# SCH_Shreder_2023-07-20.net
KiCad netlist of a schematic drawn in EasyEDA
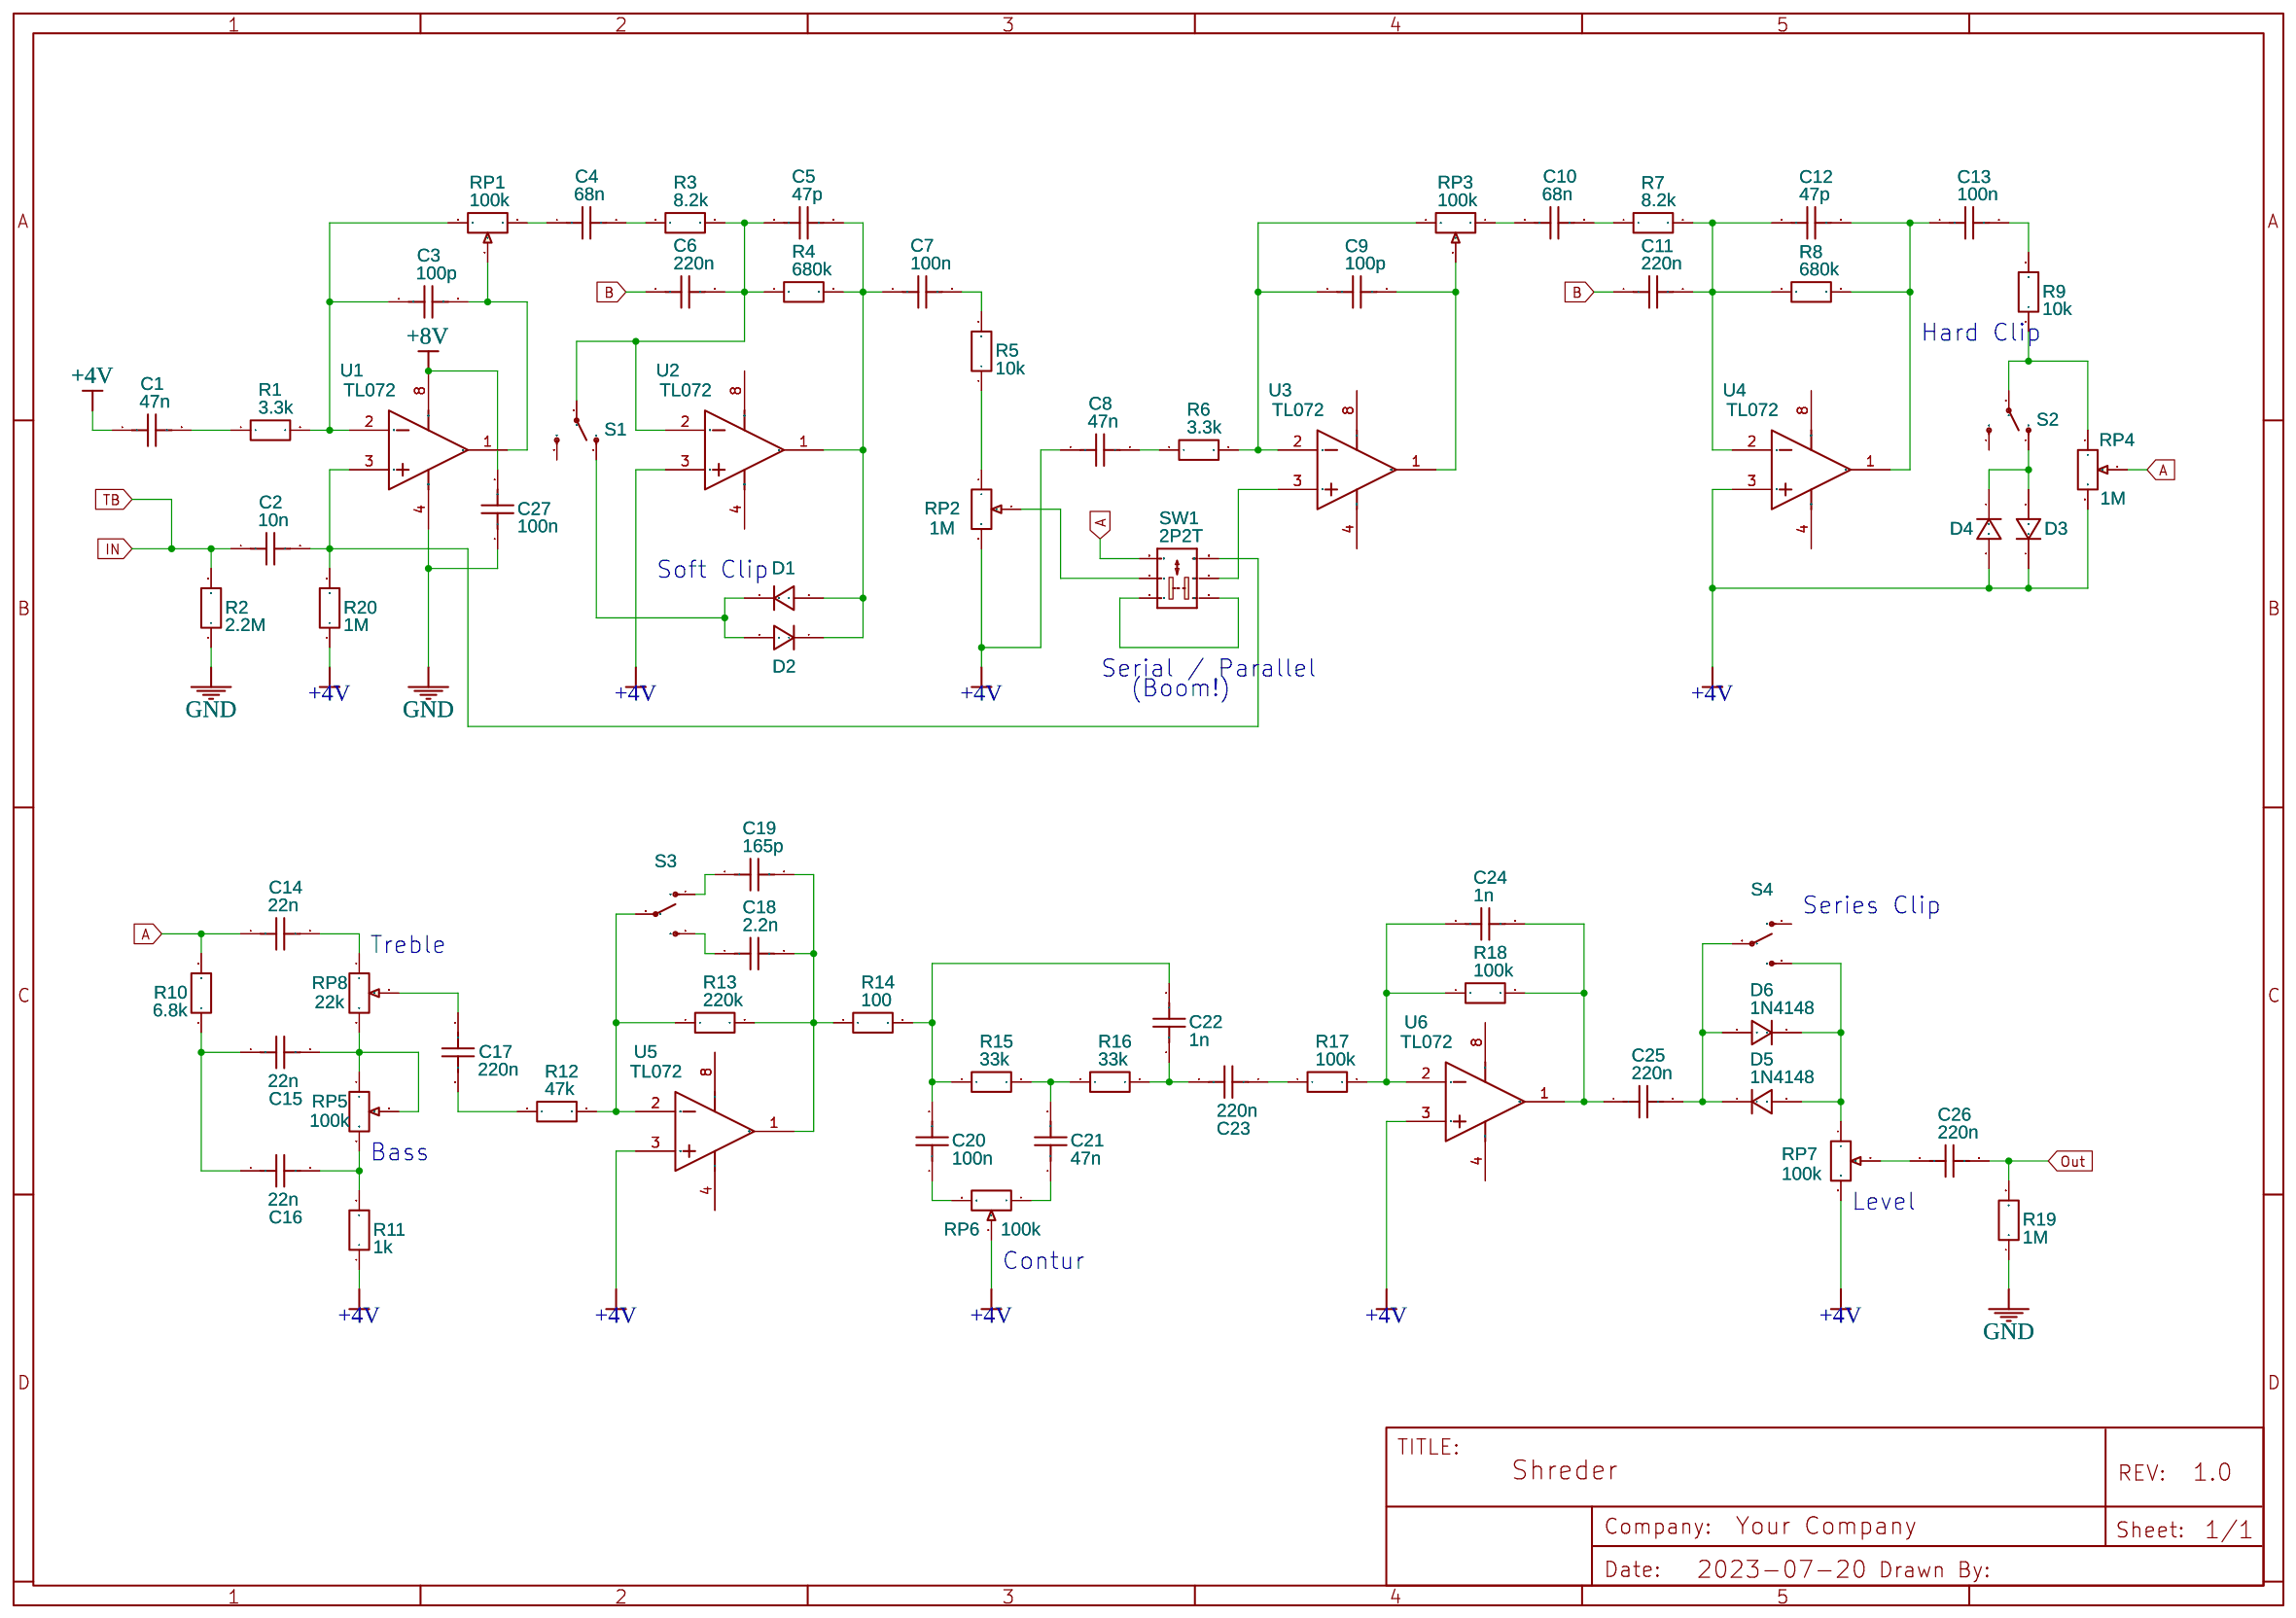
[diagram p0: Sheet_1]
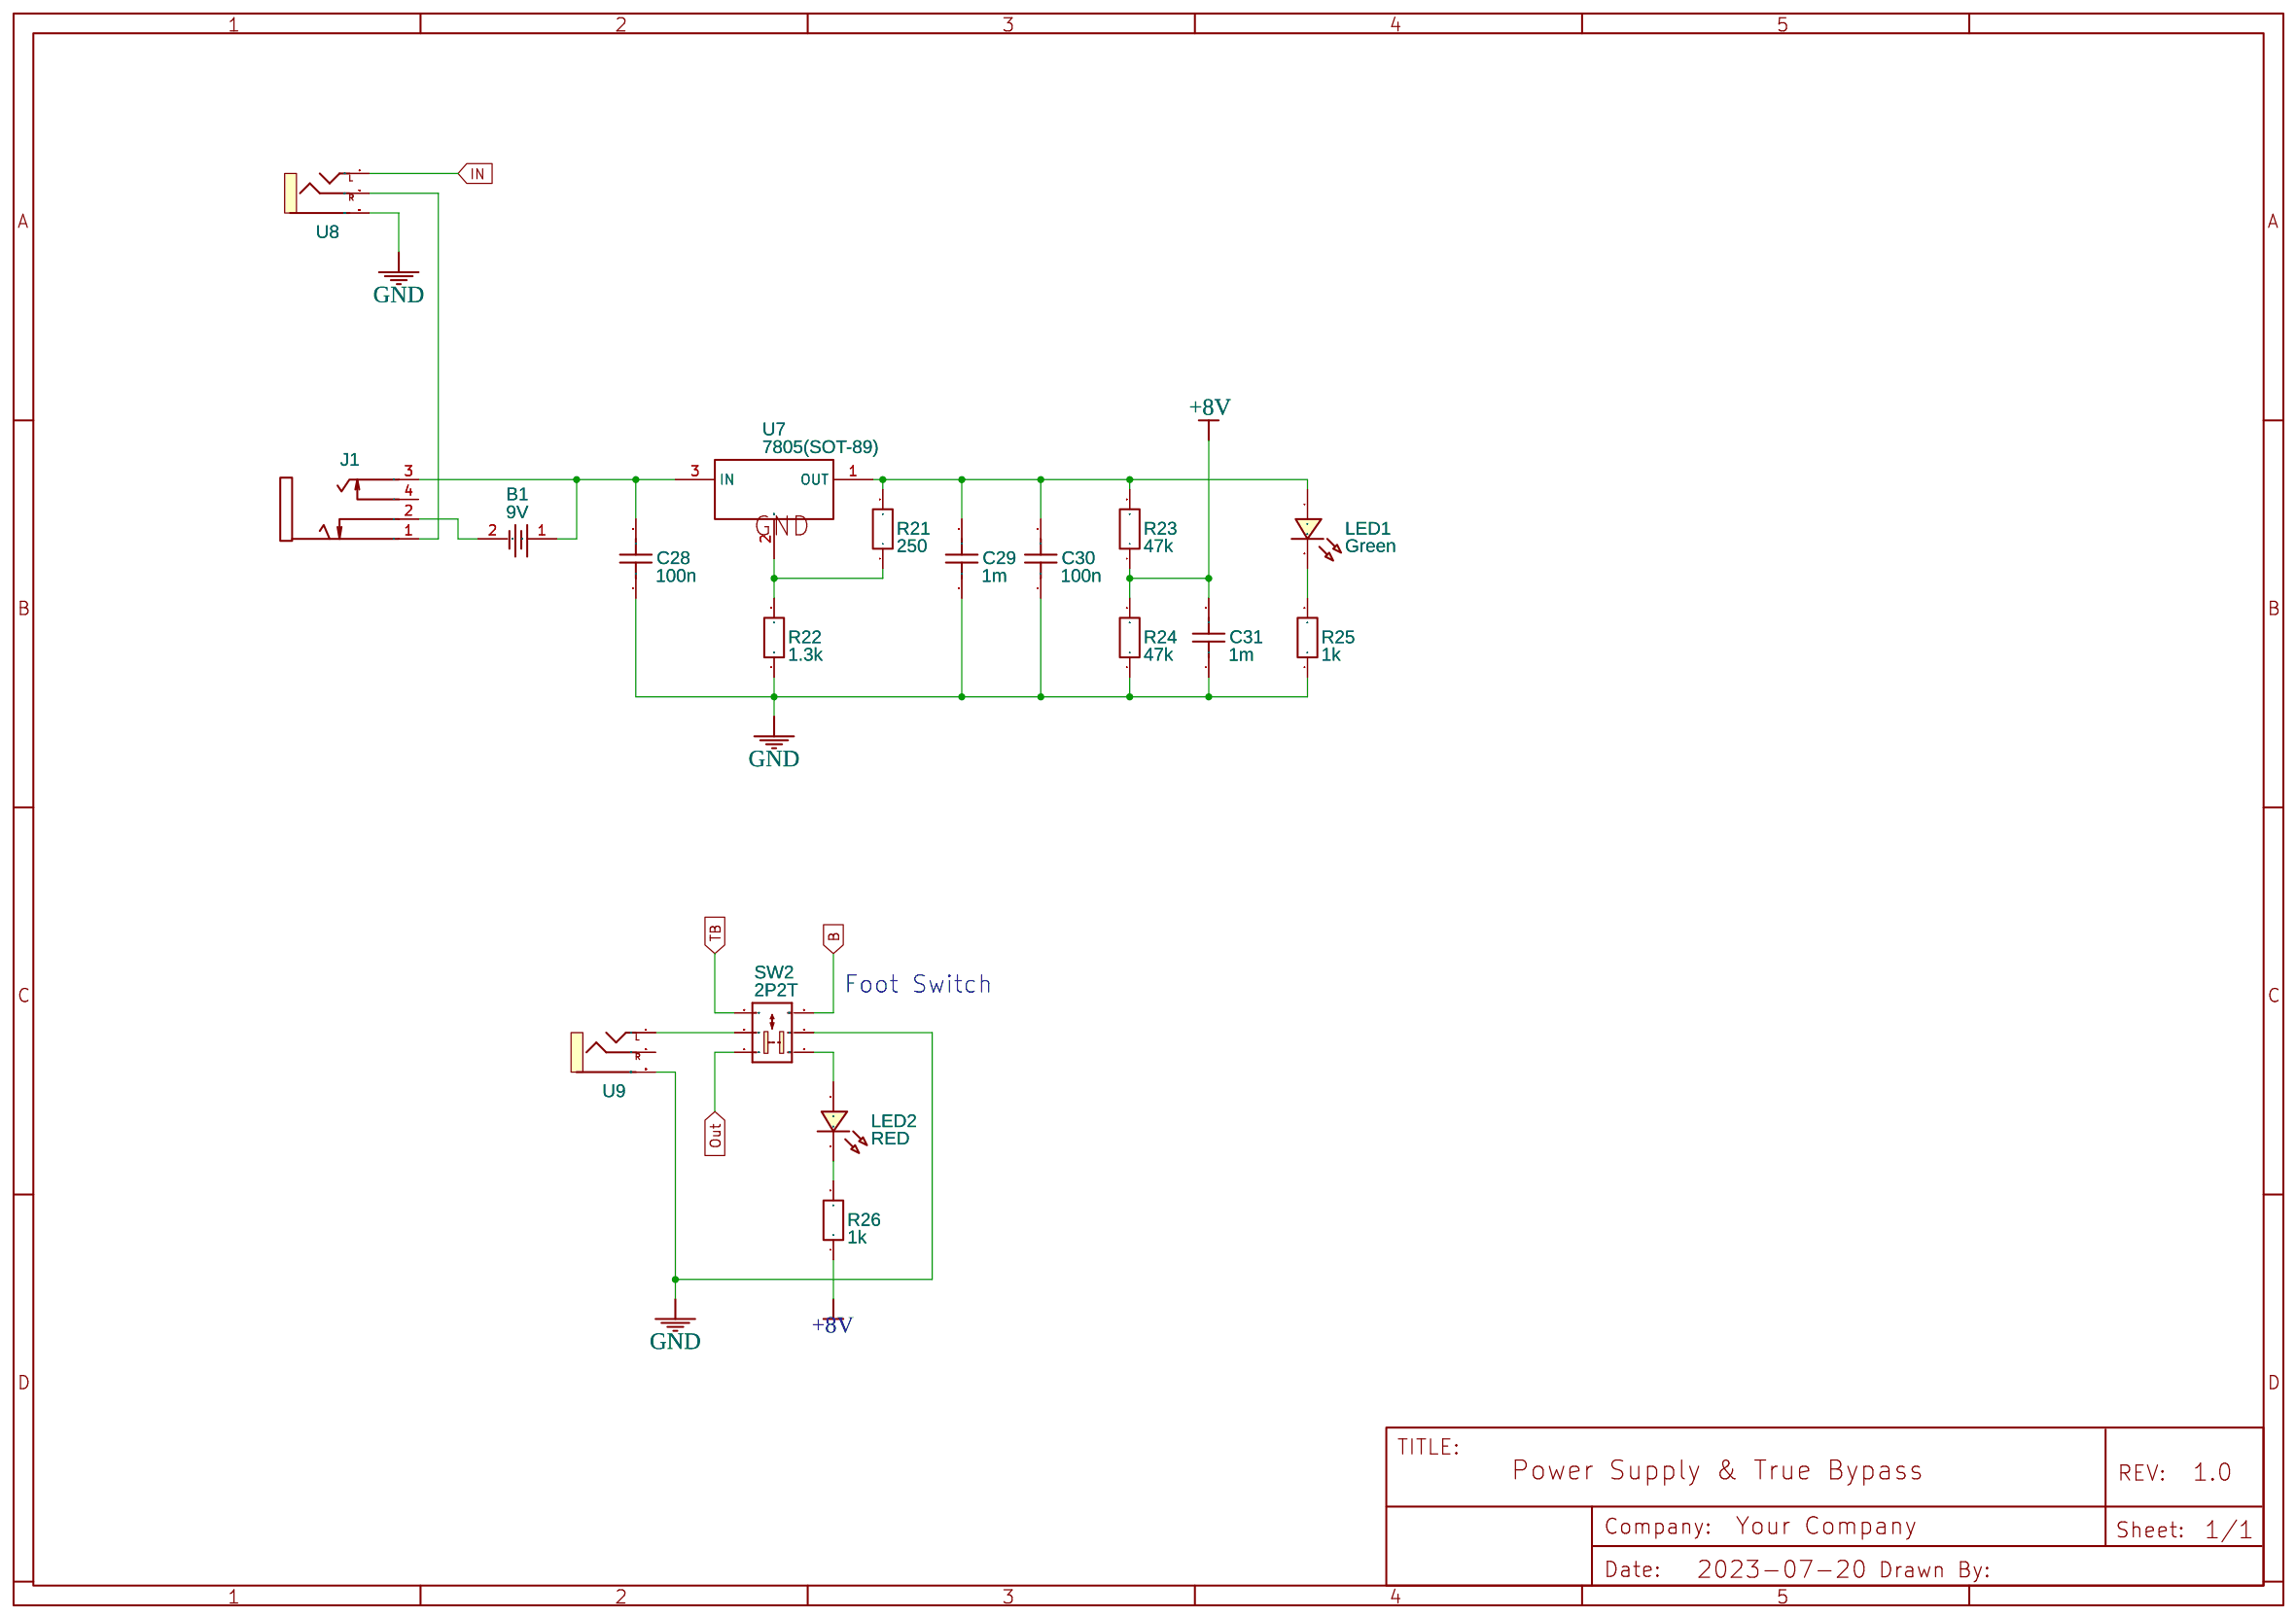
[diagram p1: Sheet_2]

(export (version "E")
  (design (tool "Eeschema 10.0.6"))
  (components
    (comp (ref "C1") (value "47n") (libsource (lib "") (part "C_RAD-0.2_US")))
    (comp (ref "C2") (value "10n") (libsource (lib "") (part "C_RAD-0.2_US")))
    (comp (ref "C3") (value "100p") (libsource (lib "") (part "C_RAD-0.2_US")))
    (comp (ref "C4") (value "68n") (libsource (lib "") (part "C_RAD-0.2_US")))
    (comp (ref "C5") (value "47p") (libsource (lib "") (part "C_RAD-0.2_US")))
    (comp (ref "C6") (value "220n") (libsource (lib "") (part "C_RAD-0.2_US")))
    (comp (ref "C7") (value "100n") (libsource (lib "") (part "C_RAD-0.2_US")))
    (comp (ref "C8") (value "47n") (libsource (lib "") (part "C_RAD-0.2_US")))
    (comp (ref "C9") (value "100p") (libsource (lib "") (part "C_RAD-0.2_US")))
    (comp (ref "C10") (value "68n") (libsource (lib "") (part "C_RAD-0.2_US")))
    (comp (ref "C11") (value "220n") (libsource (lib "") (part "C_RAD-0.2_US")))
    (comp (ref "C12") (value "47p") (libsource (lib "") (part "C_RAD-0.2_US")))
    (comp (ref "C13") (value "100n") (libsource (lib "") (part "C_RAD-0.2_US")))
    (comp (ref "C14") (value "22n") (libsource (lib "") (part "C_RAD-0.2_US")))
    (comp (ref "C15") (value "22n") (libsource (lib "") (part "C_RAD-0.2_US_3")))
    (comp (ref "C16") (value "22n") (libsource (lib "") (part "C_RAD-0.2_US_3")))
    (comp (ref "C17") (value "220n") (libsource (lib "") (part "C_RAD-0.2_US_4")))
    (comp (ref "C18") (value "2.2n") (libsource (lib "") (part "C_RAD-0.2_US")))
    (comp (ref "C19") (value "165p") (libsource (lib "") (part "C_RAD-0.2_US")))
    (comp (ref "C20") (value "100n") (libsource (lib "") (part "C_RAD-0.2_US_2")))
    (comp (ref "C21") (value "47n") (libsource (lib "") (part "C_RAD-0.2_US_2")))
    (comp (ref "C22") (value "1n") (libsource (lib "") (part "C_RAD-0.2_US_2")))
    (comp (ref "C23") (value "220n") (libsource (lib "") (part "C_RAD-0.2_US_1")))
    (comp (ref "C24") (value "1n") (libsource (lib "") (part "C_RAD-0.2_US")))
    (comp (ref "C25") (value "220n") (libsource (lib "") (part "C_RAD-0.2_US")))
    (comp (ref "C26") (value "220n") (libsource (lib "") (part "C_RAD-0.2_US")))
    (comp (ref "C27") (value "100n") (libsource (lib "") (part "C_RAD-0.2_US_2")))
    (comp (ref "D1")
      (value "1N4148")
      (fields (field (name "BOM_Supplier Part") "C13769"))
      (libsource (lib "") (part "1N4148"))
    )
    (comp (ref "D2")
      (value "1N4148")
      (fields (field (name "BOM_Supplier Part") "C13769"))
      (libsource (lib "") (part "1N4148_2"))
    )
    (comp (ref "D3")
      (value "1N4148")
      (fields (field (name "BOM_Supplier Part") "C13769"))
      (libsource (lib "") (part "1N4148_1"))
    )
    (comp (ref "D4")
      (value "1N4148")
      (fields (field (name "BOM_Supplier Part") "C13769"))
      (libsource (lib "") (part "1N4148_3"))
    )
    (comp (ref "D5")
      (value "1N4148")
      (fields (field (name "BOM_Supplier Part") "C13769"))
      (libsource (lib "") (part "1N4148"))
    )
    (comp (ref "D6")
      (value "1N4148")
      (fields (field (name "BOM_Supplier Part") "C13769"))
      (libsource (lib "") (part "1N4148_4"))
    )
    (comp (ref "R1") (value "3.3k") (libsource (lib "") (part "R_0603_EU")))
    (comp (ref "R2") (value "2.2M") (libsource (lib "") (part "R_0603_EU_1")))
    (comp (ref "R3") (value "8.2k") (libsource (lib "") (part "R_0603_EU")))
    (comp (ref "R4") (value "680k") (libsource (lib "") (part "R_0603_EU")))
    (comp (ref "R5") (value "10k") (libsource (lib "") (part "R_0603_EU_1")))
    (comp (ref "R6") (value "3.3k") (libsource (lib "") (part "R_0603_EU")))
    (comp (ref "R7") (value "8.2k") (libsource (lib "") (part "R_0603_EU")))
    (comp (ref "R8") (value "680k") (libsource (lib "") (part "R_0603_EU")))
    (comp (ref "R9") (value "10k") (libsource (lib "") (part "R_0603_EU_1")))
    (comp (ref "R10") (value "6.8k") (libsource (lib "") (part "R_0603_EU_1")))
    (comp (ref "R11") (value "1k") (libsource (lib "") (part "R_0603_EU_1")))
    (comp (ref "R12") (value "47k") (libsource (lib "") (part "R_0603_EU")))
    (comp (ref "R13") (value "220k") (libsource (lib "") (part "R_0603_EU")))
    (comp (ref "R14") (value "100") (libsource (lib "") (part "R_0603_EU")))
    (comp (ref "R15") (value "33k") (libsource (lib "") (part "R_0603_EU")))
    (comp (ref "R16") (value "33k") (libsource (lib "") (part "R_0603_EU")))
    (comp (ref "R17") (value "100k") (libsource (lib "") (part "R_0603_EU")))
    (comp (ref "R18") (value "100k") (libsource (lib "") (part "R_0603_EU")))
    (comp (ref "R19") (value "1M") (libsource (lib "") (part "R_0603_EU_1")))
    (comp (ref "R20") (value "1M") (libsource (lib "") (part "R_0603_EU_1")))
    (comp (ref "RP1") (value "100k") (libsource (lib "") (part "R_3386P_EU_1")))
    (comp (ref "RP2") (value "1M") (libsource (lib "") (part "R_3386P_EU")))
    (comp (ref "RP3") (value "100k") (libsource (lib "") (part "R_3386P_EU_1")))
    (comp (ref "RP4") (value "1M") (libsource (lib "") (part "R_3386P_EU")))
    (comp (ref "RP5") (value "100k") (libsource (lib "") (part "R_3386P_EU")))
    (comp (ref "RP6") (value "100k") (libsource (lib "") (part "R_3386P_EU_1")))
    (comp (ref "RP7") (value "100k") (libsource (lib "") (part "R_3386P_EU")))
    (comp (ref "RP8") (value "22k") (libsource (lib "") (part "R_3386P_EU")))
    (comp (ref "S1") (value "SWITCH-SPSTPTH_LOCK") (libsource (lib "") (part "SWITCH-SPSTPTH_LOCK")))
    (comp (ref "S2") (value "SWITCH-SPSTPTH_LOCK") (libsource (lib "") (part "SWITCH-SPSTPTH_LOCK")))
    (comp (ref "S3") (value "SWITCH-SPSTPTH_LOCK") (libsource (lib "") (part "SWITCH-SPSTPTH_LOCK_1")))
    (comp (ref "S4") (value "SWITCH-SPSTPTH_LOCK") (libsource (lib "") (part "SWITCH-SPSTPTH_LOCK_1")))
    (comp (ref "SW1") (value "2P2T") (libsource (lib "") (part "2P2T")))
    (comp (ref "U1")
      (value "TL072")
      (fields
        (field (name "BOM_Manufacturer Part") "TL072HIPWR")
        (field (name "BOM_Supplier Part") "C4370341")
      )
      (libsource (lib "") (part "TL072HIPWR"))
    )
    (comp (ref "U2")
      (value "TL072")
      (fields
        (field (name "BOM_Manufacturer Part") "TL072HIPWR")
        (field (name "BOM_Supplier Part") "C4370341")
      )
      (libsource (lib "") (part "TL072HIPWR"))
    )
    (comp (ref "U3")
      (value "TL072")
      (fields
        (field (name "BOM_Manufacturer Part") "TL072HIPWR")
        (field (name "BOM_Supplier Part") "C4370341")
      )
      (libsource (lib "") (part "TL072HIPWR"))
    )
    (comp (ref "U4")
      (value "TL072")
      (fields
        (field (name "BOM_Manufacturer Part") "TL072HIPWR")
        (field (name "BOM_Supplier Part") "C4370341")
      )
      (libsource (lib "") (part "TL072HIPWR"))
    )
    (comp (ref "U5")
      (value "TL072")
      (fields
        (field (name "BOM_Manufacturer Part") "TL072HIPWR")
        (field (name "BOM_Supplier Part") "C4370341")
      )
      (libsource (lib "") (part "TL072HIPWR"))
    )
    (comp (ref "U6")
      (value "TL072")
      (fields
        (field (name "BOM_Manufacturer Part") "TL072HIPWR")
        (field (name "BOM_Supplier Part") "C4370341")
      )
      (libsource (lib "") (part "TL072HIPWR"))
    )
    (comp (ref "B1")
      (value "9V")
      (fields (field (name "BOM_Manufacturer Part") "CR1220-2") (field (name "BOM_Supplier Part") "C70381"))
      (libsource (lib "") (part "CR1220-2"))
    )
    (comp (ref "C28") (value "100n") (libsource (lib "") (part "C_RAD-0.2_US")))
    (comp (ref "C29") (value "1m") (libsource (lib "") (part "C_RAD-0.2_US")))
    (comp (ref "C30") (value "100n") (libsource (lib "") (part "C_RAD-0.2_US")))
    (comp (ref "C31") (value "1m") (libsource (lib "") (part "C_RAD-0.2_US")))
    (comp (ref "J1")
      (value "6.35mm Mono Socket (PCB Mount)")
      (fields (field (name "BOM_Manufacturer Part") "449-332"))
      (libsource (lib "") (part "6.35mm Mono Socket (PCB Mount)"))
    )
    (comp (ref "LED1")
      (value "Green")
      (fields
        (field (name "BOM_Manufacturer Part") "19-217/BHC-ZL1M2RY/3T")
        (field (name "BOM_Supplier Part") "C72041")
      )
      (libsource (lib "") (part "LED-0603_B"))
    )
    (comp (ref "LED2")
      (value "RED")
      (fields
        (field (name "BOM_Manufacturer Part") "19-217/BHC-ZL1M2RY/3T")
        (field (name "BOM_Supplier Part") "C72041")
      )
      (libsource (lib "") (part "LED-0603_B"))
    )
    (comp (ref "R21") (value "250") (libsource (lib "") (part "R_0603_EU")))
    (comp (ref "R22") (value "1.3k") (libsource (lib "") (part "R_0603_EU")))
    (comp (ref "R23") (value "47k") (libsource (lib "") (part "R_0603_EU")))
    (comp (ref "R24") (value "47k") (libsource (lib "") (part "R_0603_EU")))
    (comp (ref "R25") (value "1k") (libsource (lib "") (part "R_0603_EU")))
    (comp (ref "R26") (value "1k") (libsource (lib "") (part "R_0603_EU")))
    (comp (ref "SW2") (value "2P2T") (libsource (lib "") (part "2P2T")))
    (comp (ref "U7")
      (value "7805(SOT-89)")
      (fields (field (name "BOM_Manufacturer Part") "CJ78L05") (field (name "BOM_Supplier Part") "C2079"))
      (libsource (lib "") (part "7805(SOT-89)"))
    )
    (comp (ref "U8") (value "AUDIO-JACKSMD2") (libsource (lib "") (part "AUDIO-JACKSMD2")))
    (comp (ref "U9") (value "AUDIO-JACKSMD2") (libsource (lib "") (part "AUDIO-JACKSMD2")))
  )
  (nets
    (net (code "1") (name "+4V") (class "Default")
      (node (ref "C1") (pin "1") (pinfunction "1_1") (pintype "unspecified"))
      (node (ref "C8") (pin "1") (pinfunction "1_1") (pintype "unspecified"))
      (node (ref "D3") (pin "1") (pinfunction "1_1") (pintype "unspecified"))
      (node (ref "D4") (pin "2") (pinfunction "2_2") (pintype "unspecified"))
      (node (ref "R11") (pin "1") (pinfunction "1_1") (pintype "unspecified"))
      (node (ref "R20") (pin "1") (pinfunction "1_1") (pintype "unspecified"))
      (node (ref "RP2") (pin "3") (pinfunction "3_3") (pintype "input"))
      (node (ref "RP4") (pin "3") (pinfunction "3_3") (pintype "input"))
      (node (ref "RP6") (pin "2") (pinfunction "2_2") (pintype "input"))
      (node (ref "RP7") (pin "3") (pinfunction "3_3") (pintype "input"))
      (node (ref "U2") (pin "3") (pinfunction "1IN+_3") (pintype "unspecified"))
      (node (ref "U4") (pin "3") (pinfunction "1IN+_3") (pintype "unspecified"))
      (node (ref "U5") (pin "3") (pinfunction "1IN+_3") (pintype "unspecified"))
      (node (ref "U6") (pin "3") (pinfunction "1IN+_3") (pintype "unspecified"))
    )
    (net (code "2") (name "+8V") (class "Default")
      (node (ref "C27") (pin "2") (pinfunction "2_2") (pintype "unspecified"))
      (node (ref "C31") (pin "2") (pinfunction "2_2") (pintype "unspecified"))
      (node (ref "R23") (pin "1") (pinfunction "1_1") (pintype "unspecified"))
      (node (ref "R24") (pin "2") (pinfunction "2_2") (pintype "unspecified"))
      (node (ref "R26") (pin "1") (pinfunction "1_1") (pintype "unspecified"))
      (node (ref "U1") (pin "8") (pinfunction "VCC+_8") (pintype "passive"))
    )
    (net (code "3") (name "A") (class "Default")
      (node (ref "C14") (pin "1") (pinfunction "1_1") (pintype "unspecified"))
      (node (ref "R10") (pin "2") (pinfunction "2_2") (pintype "unspecified"))
      (node (ref "RP4") (pin "2") (pinfunction "2_2") (pintype "input"))
      (node (ref "SW1") (pin "3.1") (pinfunction "3.1_3.1") (pintype "bidirectional"))
    )
    (net (code "4") (name "B") (class "Default")
      (node (ref "C11") (pin "1") (pinfunction "1_1") (pintype "unspecified"))
      (node (ref "C6") (pin "1") (pinfunction "1_1") (pintype "unspecified"))
      (node (ref "SW2") (pin "3.2") (pinfunction "3.2_3.2") (pintype "bidirectional"))
    )
    (net (code "5") (name "GND") (class "Default")
      (node (ref "C27") (pin "1") (pinfunction "1_1") (pintype "unspecified"))
      (node (ref "C28") (pin "1") (pinfunction "1_1") (pintype "unspecified"))
      (node (ref "C29") (pin "1") (pinfunction "1_1") (pintype "unspecified"))
      (node (ref "C30") (pin "1") (pinfunction "1_1") (pintype "unspecified"))
      (node (ref "C31") (pin "1") (pinfunction "1_1") (pintype "unspecified"))
      (node (ref "R19") (pin "1") (pinfunction "1_1") (pintype "unspecified"))
      (node (ref "R2") (pin "1") (pinfunction "1_1") (pintype "unspecified"))
      (node (ref "R22") (pin "1") (pinfunction "1_1") (pintype "unspecified"))
      (node (ref "R24") (pin "1") (pinfunction "1_1") (pintype "unspecified"))
      (node (ref "R25") (pin "1") (pinfunction "1_1") (pintype "unspecified"))
      (node (ref "SW2") (pin "2.2") (pinfunction "2.2_2.2") (pintype "bidirectional"))
      (node (ref "U1") (pin "4") (pinfunction "VCC-_4") (pintype "passive"))
      (node (ref "U8") (pin "SLEEVE") (pinfunction "SLEEVE_SLEEVE") (pintype "bidirectional"))
      (node (ref "U9") (pin "SLEEVE") (pinfunction "SLEEVE_SLEEVE") (pintype "bidirectional"))
    )
    (net (code "6") (name "IN") (class "Default")
      (node (ref "C2") (pin "1") (pinfunction "1_1") (pintype "unspecified"))
      (node (ref "R2") (pin "2") (pinfunction "2_2") (pintype "unspecified"))
      (node (ref "SW2") (pin "3.1") (pinfunction "3.1_3.1") (pintype "bidirectional"))
      (node (ref "U8") (pin "TIP") (pinfunction "LEFT_TIP") (pintype "bidirectional"))
    )
    (net (code "7") (name "Net-(C1-Pad2)") (class "Default")
      (node (ref "C1") (pin "2") (pinfunction "2_2") (pintype "unspecified"))
      (node (ref "R1") (pin "1") (pinfunction "1_1") (pintype "unspecified"))
    )
    (net (code "8") (name "Net-(C4-Pad1)") (class "Default")
      (node (ref "C4") (pin "1") (pinfunction "1_1") (pintype "unspecified"))
      (node (ref "RP1") (pin "1") (pinfunction "1_1") (pintype "input"))
    )
    (net (code "9") (name "Net-(C4-Pad2)") (class "Default")
      (node (ref "C4") (pin "2") (pinfunction "2_2") (pintype "unspecified"))
      (node (ref "R3") (pin "1") (pinfunction "1_1") (pintype "unspecified"))
    )
    (net (code "10") (name "Net-(C7-Pad2)") (class "Default")
      (node (ref "C7") (pin "2") (pinfunction "2_2") (pintype "unspecified"))
      (node (ref "R5") (pin "2") (pinfunction "2_2") (pintype "unspecified"))
    )
    (net (code "11") (name "Net-(C8-Pad2)") (class "Default")
      (node (ref "C8") (pin "2") (pinfunction "2_2") (pintype "unspecified"))
      (node (ref "R6") (pin "1") (pinfunction "1_1") (pintype "unspecified"))
    )
    (net (code "12") (name "Net-(C10-Pad1)") (class "Default")
      (node (ref "C10") (pin "1") (pinfunction "1_1") (pintype "unspecified"))
      (node (ref "RP3") (pin "1") (pinfunction "1_1") (pintype "input"))
    )
    (net (code "13") (name "Net-(C10-Pad2)") (class "Default")
      (node (ref "C10") (pin "2") (pinfunction "2_2") (pintype "unspecified"))
      (node (ref "R7") (pin "1") (pinfunction "1_1") (pintype "unspecified"))
    )
    (net (code "14") (name "Net-(C13-Pad2)") (class "Default")
      (node (ref "C13") (pin "2") (pinfunction "2_2") (pintype "unspecified"))
      (node (ref "R9") (pin "2") (pinfunction "2_2") (pintype "unspecified"))
    )
    (net (code "15") (name "Net-(C14-Pad2)") (class "Default")
      (node (ref "C14") (pin "2") (pinfunction "2_2") (pintype "unspecified"))
      (node (ref "RP8") (pin "1") (pinfunction "1_1") (pintype "input"))
    )
    (net (code "16") (name "Net-(C15-Pad1)") (class "Default")
      (node (ref "C15") (pin "1") (pinfunction "1_1") (pintype "unspecified"))
      (node (ref "C16") (pin "1") (pinfunction "1_1") (pintype "unspecified"))
      (node (ref "R10") (pin "1") (pinfunction "1_1") (pintype "unspecified"))
    )
    (net (code "17") (name "Net-(C15-Pad2)") (class "Default")
      (node (ref "C15") (pin "2") (pinfunction "2_2") (pintype "unspecified"))
      (node (ref "RP5") (pin "1") (pinfunction "1_1") (pintype "input"))
      (node (ref "RP5") (pin "2") (pinfunction "2_2") (pintype "input"))
      (node (ref "RP8") (pin "3") (pinfunction "3_3") (pintype "input"))
    )
    (net (code "18") (name "Net-(C16-Pad2)") (class "Default")
      (node (ref "C16") (pin "2") (pinfunction "2_2") (pintype "unspecified"))
      (node (ref "R11") (pin "2") (pinfunction "2_2") (pintype "unspecified"))
      (node (ref "RP5") (pin "3") (pinfunction "3_3") (pintype "input"))
    )
    (net (code "19") (name "Net-(C17-Pad1)") (class "Default")
      (node (ref "C17") (pin "1") (pinfunction "1_1") (pintype "unspecified"))
      (node (ref "RP8") (pin "2") (pinfunction "2_2") (pintype "input"))
    )
    (net (code "20") (name "Net-(C17-Pad2)") (class "Default")
      (node (ref "C17") (pin "2") (pinfunction "2_2") (pintype "unspecified"))
      (node (ref "R12") (pin "1") (pinfunction "1_1") (pintype "unspecified"))
    )
    (net (code "21") (name "Net-(C20-Pad1)") (class "Default")
      (node (ref "C20") (pin "1") (pinfunction "1_1") (pintype "unspecified"))
      (node (ref "RP6") (pin "3") (pinfunction "3_3") (pintype "input"))
    )
    (net (code "22") (name "Net-(C20-Pad2)") (class "Default")
      (node (ref "C20") (pin "2") (pinfunction "2_2") (pintype "unspecified"))
      (node (ref "C22") (pin "2") (pinfunction "2_2") (pintype "unspecified"))
      (node (ref "R14") (pin "2") (pinfunction "2_2") (pintype "unspecified"))
      (node (ref "R15") (pin "1") (pinfunction "1_1") (pintype "unspecified"))
    )
    (net (code "23") (name "Net-(C21-Pad1)") (class "Default")
      (node (ref "C21") (pin "1") (pinfunction "1_1") (pintype "unspecified"))
      (node (ref "RP6") (pin "1") (pinfunction "1_1") (pintype "input"))
    )
    (net (code "24") (name "Net-(C21-Pad2)") (class "Default")
      (node (ref "C21") (pin "2") (pinfunction "2_2") (pintype "unspecified"))
      (node (ref "R15") (pin "2") (pinfunction "2_2") (pintype "unspecified"))
      (node (ref "R16") (pin "1") (pinfunction "1_1") (pintype "unspecified"))
    )
    (net (code "25") (name "Net-(C22-Pad1)") (class "Default")
      (node (ref "C22") (pin "1") (pinfunction "1_1") (pintype "unspecified"))
      (node (ref "C23") (pin "2") (pinfunction "2_2") (pintype "unspecified"))
      (node (ref "R16") (pin "2") (pinfunction "2_2") (pintype "unspecified"))
    )
    (net (code "26") (name "Net-(C23-Pad1)") (class "Default")
      (node (ref "C23") (pin "1") (pinfunction "1_1") (pintype "unspecified"))
      (node (ref "R17") (pin "1") (pinfunction "1_1") (pintype "unspecified"))
    )
    (net (code "27") (name "Net-(C26-Pad1)") (class "Default")
      (node (ref "C26") (pin "1") (pinfunction "1_1") (pintype "unspecified"))
      (node (ref "RP7") (pin "2") (pinfunction "2_2") (pintype "input"))
    )
    (net (code "28") (name "Net-(J1-2)") (class "Default")
      (node (ref "J1") (pin "1") (pinfunction "2_1") (pintype "unspecified"))
      (node (ref "U8") (pin "RING") (pinfunction "RIGHT_RING") (pintype "bidirectional"))
    )
    (net (code "29") (name "Net-(J1-3)") (class "Default")
      (node (ref "B1") (pin "2") (pinfunction "2_2") (pintype "input"))
      (node (ref "J1") (pin "2") (pinfunction "3_2") (pintype "unspecified"))
    )
    (net (code "30") (name "Net-(J1-6)") (class "Default")
      (node (ref "B1") (pin "1") (pinfunction "1_1") (pintype "input"))
      (node (ref "C28") (pin "2") (pinfunction "2_2") (pintype "unspecified"))
      (node (ref "J1") (pin "3") (pinfunction "6_3") (pintype "unspecified"))
      (node (ref "U7") (pin "3") (pinfunction "IN_3") (pintype "passive"))
    )
    (net (code "31") (name "Net-(LED1-Pad2)") (class "Default")
      (node (ref "LED1") (pin "2") (pinfunction "2_2") (pintype "unspecified"))
      (node (ref "R25") (pin "2") (pinfunction "2_2") (pintype "unspecified"))
    )
    (net (code "32") (name "Net-(LED2-Pad1)") (class "Default")
      (node (ref "LED2") (pin "1") (pinfunction "1_1") (pintype "unspecified"))
      (node (ref "SW2") (pin "1.2") (pinfunction "1.2_1.2") (pintype "bidirectional"))
    )
    (net (code "33") (name "Net-(LED2-Pad2)") (class "Default")
      (node (ref "LED2") (pin "2") (pinfunction "2_2") (pintype "unspecified"))
      (node (ref "R26") (pin "2") (pinfunction "2_2") (pintype "unspecified"))
    )
    (net (code "34") (name "Net-(R5-Pad1)") (class "Default")
      (node (ref "R5") (pin "1") (pinfunction "1_1") (pintype "unspecified"))
      (node (ref "RP2") (pin "1") (pinfunction "1_1") (pintype "input"))
    )
    (net (code "35") (name "Net-(RP2-Pad2)") (class "Default")
      (node (ref "RP2") (pin "2") (pinfunction "2_2") (pintype "input"))
      (node (ref "SW1") (pin "2.1") (pinfunction "2.1_2.1") (pintype "bidirectional"))
    )
    (net (code "36") (name "Net-(S1-O)") (class "Default")
      (node (ref "D1") (pin "1") (pinfunction "1_1") (pintype "unspecified"))
      (node (ref "D2") (pin "2") (pinfunction "2_2") (pintype "unspecified"))
      (node (ref "S1") (pin "1") (pinfunction "O_1") (pintype "unspecified"))
    )
    (net (code "37") (name "Net-(S1-P)") (class "Default")
      (node (ref "C5") (pin "1") (pinfunction "1_1") (pintype "unspecified"))
      (node (ref "C6") (pin "2") (pinfunction "2_2") (pintype "unspecified"))
      (node (ref "R3") (pin "2") (pinfunction "2_2") (pintype "unspecified"))
      (node (ref "R4") (pin "1") (pinfunction "1_1") (pintype "unspecified"))
      (node (ref "S1") (pin "2") (pinfunction "P_2") (pintype "unspecified"))
      (node (ref "U2") (pin "2") (pinfunction "1IN-_2") (pintype "unspecified"))
    )
    (net (code "38") (name "Net-(S2-O)") (class "Default")
      (node (ref "D3") (pin "2") (pinfunction "2_2") (pintype "unspecified"))
      (node (ref "D4") (pin "1") (pinfunction "1_1") (pintype "unspecified"))
      (node (ref "S2") (pin "1") (pinfunction "O_1") (pintype "unspecified"))
    )
    (net (code "39") (name "Net-(S2-P)") (class "Default")
      (node (ref "R9") (pin "1") (pinfunction "1_1") (pintype "unspecified"))
      (node (ref "RP4") (pin "1") (pinfunction "1_1") (pintype "input"))
      (node (ref "S2") (pin "2") (pinfunction "P_2") (pintype "unspecified"))
    )
    (net (code "40") (name "Net-(S3-O)") (class "Default")
      (node (ref "C19") (pin "1") (pinfunction "1_1") (pintype "unspecified"))
      (node (ref "S3") (pin "1") (pinfunction "O_1") (pintype "unspecified"))
    )
    (net (code "41") (name "Net-(S3-P)") (class "Default")
      (node (ref "R12") (pin "2") (pinfunction "2_2") (pintype "unspecified"))
      (node (ref "R13") (pin "1") (pinfunction "1_1") (pintype "unspecified"))
      (node (ref "S3") (pin "2") (pinfunction "P_2") (pintype "unspecified"))
      (node (ref "U5") (pin "2") (pinfunction "1IN-_2") (pintype "unspecified"))
    )
    (net (code "42") (name "Net-(S3-S)") (class "Default")
      (node (ref "C18") (pin "1") (pinfunction "1_1") (pintype "unspecified"))
      (node (ref "S3") (pin "3") (pinfunction "S_3") (pintype "unspecified"))
    )
    (net (code "43") (name "Net-(S4-P)") (class "Default")
      (node (ref "C25") (pin "2") (pinfunction "2_2") (pintype "unspecified"))
      (node (ref "D5") (pin "1") (pinfunction "1_1") (pintype "unspecified"))
      (node (ref "D6") (pin "2") (pinfunction "2_2") (pintype "unspecified"))
      (node (ref "S4") (pin "2") (pinfunction "P_2") (pintype "unspecified"))
    )
    (net (code "44") (name "Net-(S4-S)") (class "Default")
      (node (ref "D5") (pin "2") (pinfunction "2_2") (pintype "unspecified"))
      (node (ref "D6") (pin "1") (pinfunction "1_1") (pintype "unspecified"))
      (node (ref "RP7") (pin "1") (pinfunction "1_1") (pintype "input"))
      (node (ref "S4") (pin "3") (pinfunction "S_3") (pintype "unspecified"))
    )
    (net (code "45") (name "Net-(SW1-Pad1.1)") (class "Default")
      (node (ref "SW1") (pin "1.1") (pinfunction "1.1_1.1") (pintype "bidirectional"))
      (node (ref "SW1") (pin "1.2") (pinfunction "1.2_1.2") (pintype "bidirectional"))
    )
    (net (code "46") (name "Net-(U1-1IN+)") (class "Default")
      (node (ref "C2") (pin "2") (pinfunction "2_2") (pintype "unspecified"))
      (node (ref "R20") (pin "2") (pinfunction "2_2") (pintype "unspecified"))
      (node (ref "SW1") (pin "3.2") (pinfunction "3.2_3.2") (pintype "bidirectional"))
      (node (ref "U1") (pin "3") (pinfunction "1IN+_3") (pintype "unspecified"))
    )
    (net (code "47") (name "Net-(U1-1IN-)") (class "Default")
      (node (ref "C3") (pin "1") (pinfunction "1_1") (pintype "unspecified"))
      (node (ref "R1") (pin "2") (pinfunction "2_2") (pintype "unspecified"))
      (node (ref "RP1") (pin "3") (pinfunction "3_3") (pintype "input"))
      (node (ref "U1") (pin "2") (pinfunction "1IN-_2") (pintype "unspecified"))
    )
    (net (code "48") (name "Net-(U1-1OUT)") (class "Default")
      (node (ref "C3") (pin "2") (pinfunction "2_2") (pintype "unspecified"))
      (node (ref "RP1") (pin "2") (pinfunction "2_2") (pintype "input"))
      (node (ref "U1") (pin "1") (pinfunction "1OUT_1") (pintype "output"))
    )
    (net (code "49") (name "Net-(U2-1OUT)") (class "Default")
      (node (ref "C5") (pin "2") (pinfunction "2_2") (pintype "unspecified"))
      (node (ref "C7") (pin "1") (pinfunction "1_1") (pintype "unspecified"))
      (node (ref "D1") (pin "2") (pinfunction "2_2") (pintype "unspecified"))
      (node (ref "D2") (pin "1") (pinfunction "1_1") (pintype "unspecified"))
      (node (ref "R4") (pin "2") (pinfunction "2_2") (pintype "unspecified"))
      (node (ref "U2") (pin "1") (pinfunction "1OUT_1") (pintype "output"))
    )
    (net (code "50") (name "Net-(U3-1IN+)") (class "Default")
      (node (ref "SW1") (pin "2.2") (pinfunction "2.2_2.2") (pintype "bidirectional"))
      (node (ref "U3") (pin "3") (pinfunction "1IN+_3") (pintype "unspecified"))
    )
    (net (code "51") (name "Net-(U3-1IN-)") (class "Default")
      (node (ref "C9") (pin "1") (pinfunction "1_1") (pintype "unspecified"))
      (node (ref "R6") (pin "2") (pinfunction "2_2") (pintype "unspecified"))
      (node (ref "RP3") (pin "3") (pinfunction "3_3") (pintype "input"))
      (node (ref "U3") (pin "2") (pinfunction "1IN-_2") (pintype "unspecified"))
    )
    (net (code "52") (name "Net-(U3-1OUT)") (class "Default")
      (node (ref "C9") (pin "2") (pinfunction "2_2") (pintype "unspecified"))
      (node (ref "RP3") (pin "2") (pinfunction "2_2") (pintype "input"))
      (node (ref "U3") (pin "1") (pinfunction "1OUT_1") (pintype "output"))
    )
    (net (code "53") (name "Net-(U4-1IN-)") (class "Default")
      (node (ref "C11") (pin "2") (pinfunction "2_2") (pintype "unspecified"))
      (node (ref "C12") (pin "1") (pinfunction "1_1") (pintype "unspecified"))
      (node (ref "R7") (pin "2") (pinfunction "2_2") (pintype "unspecified"))
      (node (ref "R8") (pin "1") (pinfunction "1_1") (pintype "unspecified"))
      (node (ref "U4") (pin "2") (pinfunction "1IN-_2") (pintype "unspecified"))
    )
    (net (code "54") (name "Net-(U4-1OUT)") (class "Default")
      (node (ref "C12") (pin "2") (pinfunction "2_2") (pintype "unspecified"))
      (node (ref "C13") (pin "1") (pinfunction "1_1") (pintype "unspecified"))
      (node (ref "R8") (pin "2") (pinfunction "2_2") (pintype "unspecified"))
      (node (ref "U4") (pin "1") (pinfunction "1OUT_1") (pintype "output"))
    )
    (net (code "55") (name "Net-(U5-1OUT)") (class "Default")
      (node (ref "C18") (pin "2") (pinfunction "2_2") (pintype "unspecified"))
      (node (ref "C19") (pin "2") (pinfunction "2_2") (pintype "unspecified"))
      (node (ref "R13") (pin "2") (pinfunction "2_2") (pintype "unspecified"))
      (node (ref "R14") (pin "1") (pinfunction "1_1") (pintype "unspecified"))
      (node (ref "U5") (pin "1") (pinfunction "1OUT_1") (pintype "output"))
    )
    (net (code "56") (name "Net-(U6-1IN-)") (class "Default")
      (node (ref "C24") (pin "1") (pinfunction "1_1") (pintype "unspecified"))
      (node (ref "R17") (pin "2") (pinfunction "2_2") (pintype "unspecified"))
      (node (ref "R18") (pin "1") (pinfunction "1_1") (pintype "unspecified"))
      (node (ref "U6") (pin "2") (pinfunction "1IN-_2") (pintype "unspecified"))
    )
    (net (code "57") (name "Net-(U6-1OUT)") (class "Default")
      (node (ref "C24") (pin "2") (pinfunction "2_2") (pintype "unspecified"))
      (node (ref "C25") (pin "1") (pinfunction "1_1") (pintype "unspecified"))
      (node (ref "R18") (pin "2") (pinfunction "2_2") (pintype "unspecified"))
      (node (ref "U6") (pin "1") (pinfunction "1OUT_1") (pintype "output"))
    )
    (net (code "58") (name "Net-(U7-GND)") (class "Default")
      (node (ref "R21") (pin "1") (pinfunction "1_1") (pintype "unspecified"))
      (node (ref "R22") (pin "2") (pinfunction "2_2") (pintype "unspecified"))
      (node (ref "U7") (pin "2") (pinfunction "GND_2") (pintype "passive"))
    )
    (net (code "59") (name "Net-(U7-OUT)") (class "Default")
      (node (ref "C29") (pin "2") (pinfunction "2_2") (pintype "unspecified"))
      (node (ref "C30") (pin "2") (pinfunction "2_2") (pintype "unspecified"))
      (node (ref "LED1") (pin "1") (pinfunction "1_1") (pintype "unspecified"))
      (node (ref "R21") (pin "2") (pinfunction "2_2") (pintype "unspecified"))
      (node (ref "R23") (pin "2") (pinfunction "2_2") (pintype "unspecified"))
      (node (ref "U7") (pin "1") (pinfunction "OUT_1") (pintype "passive"))
    )
    (net (code "60") (name "Net-(U9-LEFT)") (class "Default")
      (node (ref "SW2") (pin "2.1") (pinfunction "2.1_2.1") (pintype "bidirectional"))
      (node (ref "U9") (pin "TIP") (pinfunction "LEFT_TIP") (pintype "bidirectional"))
    )
    (net (code "61") (name "Out") (class "Default")
      (node (ref "C26") (pin "2") (pinfunction "2_2") (pintype "unspecified"))
      (node (ref "R19") (pin "2") (pinfunction "2_2") (pintype "unspecified"))
      (node (ref "SW2") (pin "1.1") (pinfunction "1.1_1.1") (pintype "bidirectional"))
    )
    (net (code "62") (name "unconnected-(J1-7-Pad4)") (class "Default")
      (node (ref "J1") (pin "4") (pinfunction "7_4") (pintype "unspecified"))
    )
    (net (code "63") (name "unconnected-(S1-S-Pad3)") (class "Default")
      (node (ref "S1") (pin "3") (pinfunction "S_3") (pintype "unspecified"))
    )
    (net (code "64") (name "unconnected-(S2-S-Pad3)") (class "Default")
      (node (ref "S2") (pin "3") (pinfunction "S_3") (pintype "unspecified"))
    )
    (net (code "65") (name "unconnected-(S4-O-Pad1)") (class "Default")
      (node (ref "S4") (pin "1") (pinfunction "O_1") (pintype "unspecified"))
    )
    (net (code "66") (name "unconnected-(U2-VCC+-Pad8)") (class "Default")
      (node (ref "U2") (pin "8") (pinfunction "VCC+_8") (pintype "passive"))
    )
    (net (code "67") (name "unconnected-(U2-VCC--Pad4)") (class "Default")
      (node (ref "U2") (pin "4") (pinfunction "VCC-_4") (pintype "passive"))
    )
    (net (code "68") (name "unconnected-(U3-VCC+-Pad8)") (class "Default")
      (node (ref "U3") (pin "8") (pinfunction "VCC+_8") (pintype "passive"))
    )
    (net (code "69") (name "unconnected-(U3-VCC--Pad4)") (class "Default")
      (node (ref "U3") (pin "4") (pinfunction "VCC-_4") (pintype "passive"))
    )
    (net (code "70") (name "unconnected-(U4-VCC+-Pad8)") (class "Default")
      (node (ref "U4") (pin "8") (pinfunction "VCC+_8") (pintype "passive"))
    )
    (net (code "71") (name "unconnected-(U4-VCC--Pad4)") (class "Default")
      (node (ref "U4") (pin "4") (pinfunction "VCC-_4") (pintype "passive"))
    )
    (net (code "72") (name "unconnected-(U5-VCC+-Pad8)") (class "Default")
      (node (ref "U5") (pin "8") (pinfunction "VCC+_8") (pintype "passive"))
    )
    (net (code "73") (name "unconnected-(U5-VCC--Pad4)") (class "Default")
      (node (ref "U5") (pin "4") (pinfunction "VCC-_4") (pintype "passive"))
    )
    (net (code "74") (name "unconnected-(U6-VCC+-Pad8)") (class "Default")
      (node (ref "U6") (pin "8") (pinfunction "VCC+_8") (pintype "passive"))
    )
    (net (code "75") (name "unconnected-(U6-VCC--Pad4)") (class "Default")
      (node (ref "U6") (pin "4") (pinfunction "VCC-_4") (pintype "passive"))
    )
    (net (code "76") (name "unconnected-(U9-RIGHT-PadRING)") (class "Default")
      (node (ref "U9") (pin "RING") (pinfunction "RIGHT_RING") (pintype "bidirectional"))
    )
  )
)
